# hellomax2.net
KiCad netlist of a schematic drawn in EAGLE
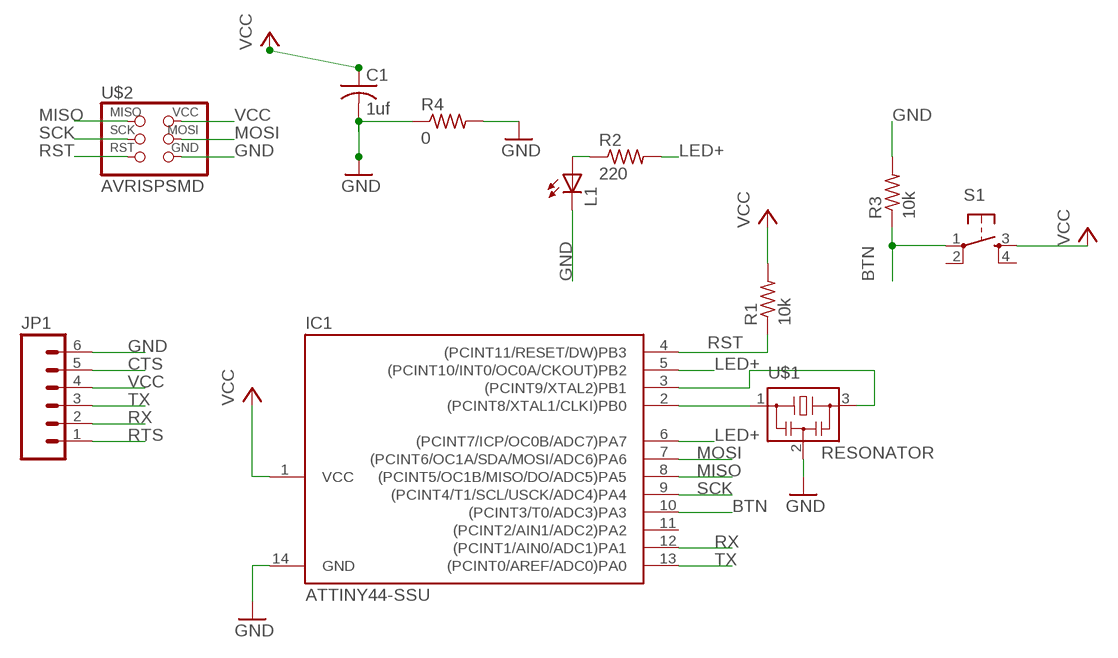
[diagram p0: schematic, sheet 1]

(export (version "E")
  (design (tool "Eeschema 10.0.6"))
  (components
    (comp (ref "C1")
      (value "1uf")
      (footprint "eagle-import:C1206")
      (libsource (lib "eagle-import") (part "C-USC1206"))
    )
    (comp (ref "IC1")
      (value "ATTINY44-SSU")
      (footprint "eagle-import:SOIC14")
      (libsource (lib "eagle-import") (part "ATTINY44-SSU"))
    )
    (comp (ref "JP1")
      (value "M06SMD")
      (footprint "eagle-import:1X06-SMD")
      (libsource (lib "eagle-import") (part "M06SMD"))
    )
    (comp (ref "L1")
      (value "LED1206")
      (footprint "eagle-import:1206")
      (libsource (lib "eagle-import") (part "LED1206"))
    )
    (comp (ref "R1")
      (value "10k")
      (footprint "eagle-import:R1206")
      (libsource (lib "eagle-import") (part "R-US_R1206"))
    )
    (comp (ref "R2")
      (value "220")
      (footprint "eagle-import:1206")
      (libsource (lib "eagle-import") (part "RESISTOR1206"))
    )
    (comp (ref "R3")
      (value "10k")
      (footprint "eagle-import:R1206")
      (libsource (lib "eagle-import") (part "R-US_R1206"))
    )
    (comp (ref "R4")
      (value "0")
      (footprint "eagle-import:1206")
      (libsource (lib "eagle-import") (part "RESISTOR1206"))
    )
    (comp (ref "S1")
      (value "6MM_SWITCH6MM_SWITCH")
      (footprint "eagle-import:6MM_SWITCH")
      (libsource (lib "eagle-import") (part "6MM_SWITCH6MM_SWITCH"))
    )
    (comp (ref "U$1")
      (value "RESONATOR")
      (footprint "eagle-import:EFOBM")
      (libsource (lib "eagle-import") (part "RESONATOR"))
    )
    (comp (ref "U$2")
      (value "AVRISPSMD")
      (footprint "eagle-import:2X03SMD")
      (libsource (lib "eagle-import") (part "AVRISPSMD"))
    )
  )
  (nets
    (net (code "1") (name "/BTN") (class "Default")
      (node (ref "IC1") (pin "10") (pinfunction "(PCINT3/T0/ADC3)PA3_10") (pintype "bidirectional"))
      (node (ref "R3") (pin "1") (pinfunction "1_1") (pintype "passive"))
      (node (ref "S1") (pin "1") (pinfunction "P_1") (pintype "passive"))
    )
    (net (code "2") (name "/CTS") (class "Default")
      (node (ref "JP1") (pin "5") (pinfunction "5_5") (pintype "passive"))
    )
    (net (code "3") (name "/LED+") (class "Default")
      (node (ref "IC1") (pin "5") (pinfunction "(PCINT10/INT0/OC0A/CKOUT)PB2_5") (pintype "bidirectional"))
      (node (ref "IC1") (pin "6") (pinfunction "(PCINT7/ICP/OC0B/ADC7)PA7_6") (pintype "bidirectional"))
      (node (ref "R2") (pin "2") (pinfunction "2_2") (pintype "passive"))
    )
    (net (code "4") (name "/MISO") (class "Default")
      (node (ref "IC1") (pin "8") (pinfunction "(PCINT5/OC1B/MISO/DO/ADC5)PA5_8") (pintype "bidirectional"))
      (node (ref "U$2") (pin "1") (pinfunction "MISO_1") (pintype "passive"))
    )
    (net (code "5") (name "/MOSI") (class "Default")
      (node (ref "IC1") (pin "7") (pinfunction "(PCINT6/OC1A/SDA/MOSI/ADC6)PA6_7") (pintype "bidirectional"))
      (node (ref "U$2") (pin "4") (pinfunction "MOSI_4") (pintype "passive"))
    )
    (net (code "6") (name "/RST") (class "Default")
      (node (ref "IC1") (pin "4") (pinfunction "(PCINT11/RESET/DW)PB3_4") (pintype "bidirectional"))
      (node (ref "R1") (pin "1") (pinfunction "1_1") (pintype "passive"))
      (node (ref "U$2") (pin "5") (pinfunction "RST_5") (pintype "passive"))
    )
    (net (code "7") (name "/RTS") (class "Default")
      (node (ref "JP1") (pin "1") (pinfunction "1_1") (pintype "passive"))
    )
    (net (code "8") (name "/RX") (class "Default")
      (node (ref "IC1") (pin "12") (pinfunction "(PCINT1/AIN0/ADC1)PA1_12") (pintype "bidirectional"))
      (node (ref "JP1") (pin "2") (pinfunction "2_2") (pintype "passive"))
    )
    (net (code "9") (name "/SCK") (class "Default")
      (node (ref "IC1") (pin "9") (pinfunction "(PCINT4/T1/SCL/USCK/ADC4)PA4_9") (pintype "bidirectional"))
      (node (ref "U$2") (pin "3") (pinfunction "SCK_3") (pintype "passive"))
    )
    (net (code "10") (name "/TX") (class "Default")
      (node (ref "IC1") (pin "13") (pinfunction "(PCINT0/AREF/ADC0)PA0_13") (pintype "bidirectional"))
      (node (ref "JP1") (pin "3") (pinfunction "3_3") (pintype "passive"))
    )
    (net (code "11") (name "GND") (class "Default")
      (node (ref "C1") (pin "2") (pinfunction "2_2") (pintype "passive"))
      (node (ref "IC1") (pin "14") (pinfunction "GND_14") (pintype "power_in"))
      (node (ref "JP1") (pin "6") (pinfunction "6_6") (pintype "passive"))
      (node (ref "L1") (pin "2") (pinfunction "C_2") (pintype "passive"))
      (node (ref "R3") (pin "2") (pinfunction "2_2") (pintype "passive"))
      (node (ref "R4") (pin "1") (pinfunction "1_1") (pintype "passive"))
      (node (ref "R4") (pin "2") (pinfunction "2_2") (pintype "passive"))
      (node (ref "U$1") (pin "2") (pinfunction "2_2") (pintype "passive"))
      (node (ref "U$2") (pin "6") (pinfunction "GND_6") (pintype "passive"))
    )
    (net (code "12") (name "Net-(IC1-(PCINT8{slash}XTAL1{slash}CLKI)PB0)") (class "Default")
      (node (ref "IC1") (pin "2") (pinfunction "(PCINT8/XTAL1/CLKI)PB0_2") (pintype "bidirectional"))
      (node (ref "U$1") (pin "1") (pinfunction "1_1") (pintype "passive"))
    )
    (net (code "13") (name "Net-(IC1-(PCINT9{slash}XTAL2)PB1)") (class "Default")
      (node (ref "IC1") (pin "3") (pinfunction "(PCINT9/XTAL2)PB1_3") (pintype "bidirectional"))
      (node (ref "U$1") (pin "3") (pinfunction "3_3") (pintype "passive"))
    )
    (net (code "14") (name "Net-(L1-A)") (class "Default")
      (node (ref "L1") (pin "1") (pinfunction "A_1") (pintype "passive"))
      (node (ref "R2") (pin "1") (pinfunction "1_1") (pintype "passive"))
    )
    (net (code "15") (name "VCC") (class "Default")
      (node (ref "C1") (pin "1") (pinfunction "1_1") (pintype "passive"))
      (node (ref "IC1") (pin "1") (pinfunction "VCC_1") (pintype "power_in"))
      (node (ref "JP1") (pin "4") (pinfunction "4_4") (pintype "passive"))
      (node (ref "R1") (pin "2") (pinfunction "2_2") (pintype "passive"))
      (node (ref "S1") (pin "3") (pinfunction "S_3") (pintype "passive"))
      (node (ref "U$2") (pin "2") (pinfunction "VCC_2") (pintype "passive"))
    )
    (net (code "16") (name "unconnected-(IC1-(PCINT2{slash}AIN1{slash}ADC2)PA2-Pad11)") (class "Default")
      (node (ref "IC1") (pin "11") (pinfunction "(PCINT2/AIN1/ADC2)PA2_11") (pintype "bidirectional"))
    )
    (net (code "17") (name "unconnected-(S1-P1-Pad2)") (class "Default")
      (node (ref "S1") (pin "2") (pinfunction "P1_2") (pintype "passive"))
    )
    (net (code "18") (name "unconnected-(S1-S1-Pad4)") (class "Default")
      (node (ref "S1") (pin "4") (pinfunction "S1_4") (pintype "passive"))
    )
  )
)
